# 3_Channel_Preprocessor.net
KiCad netlist of a schematic drawn in EAGLE
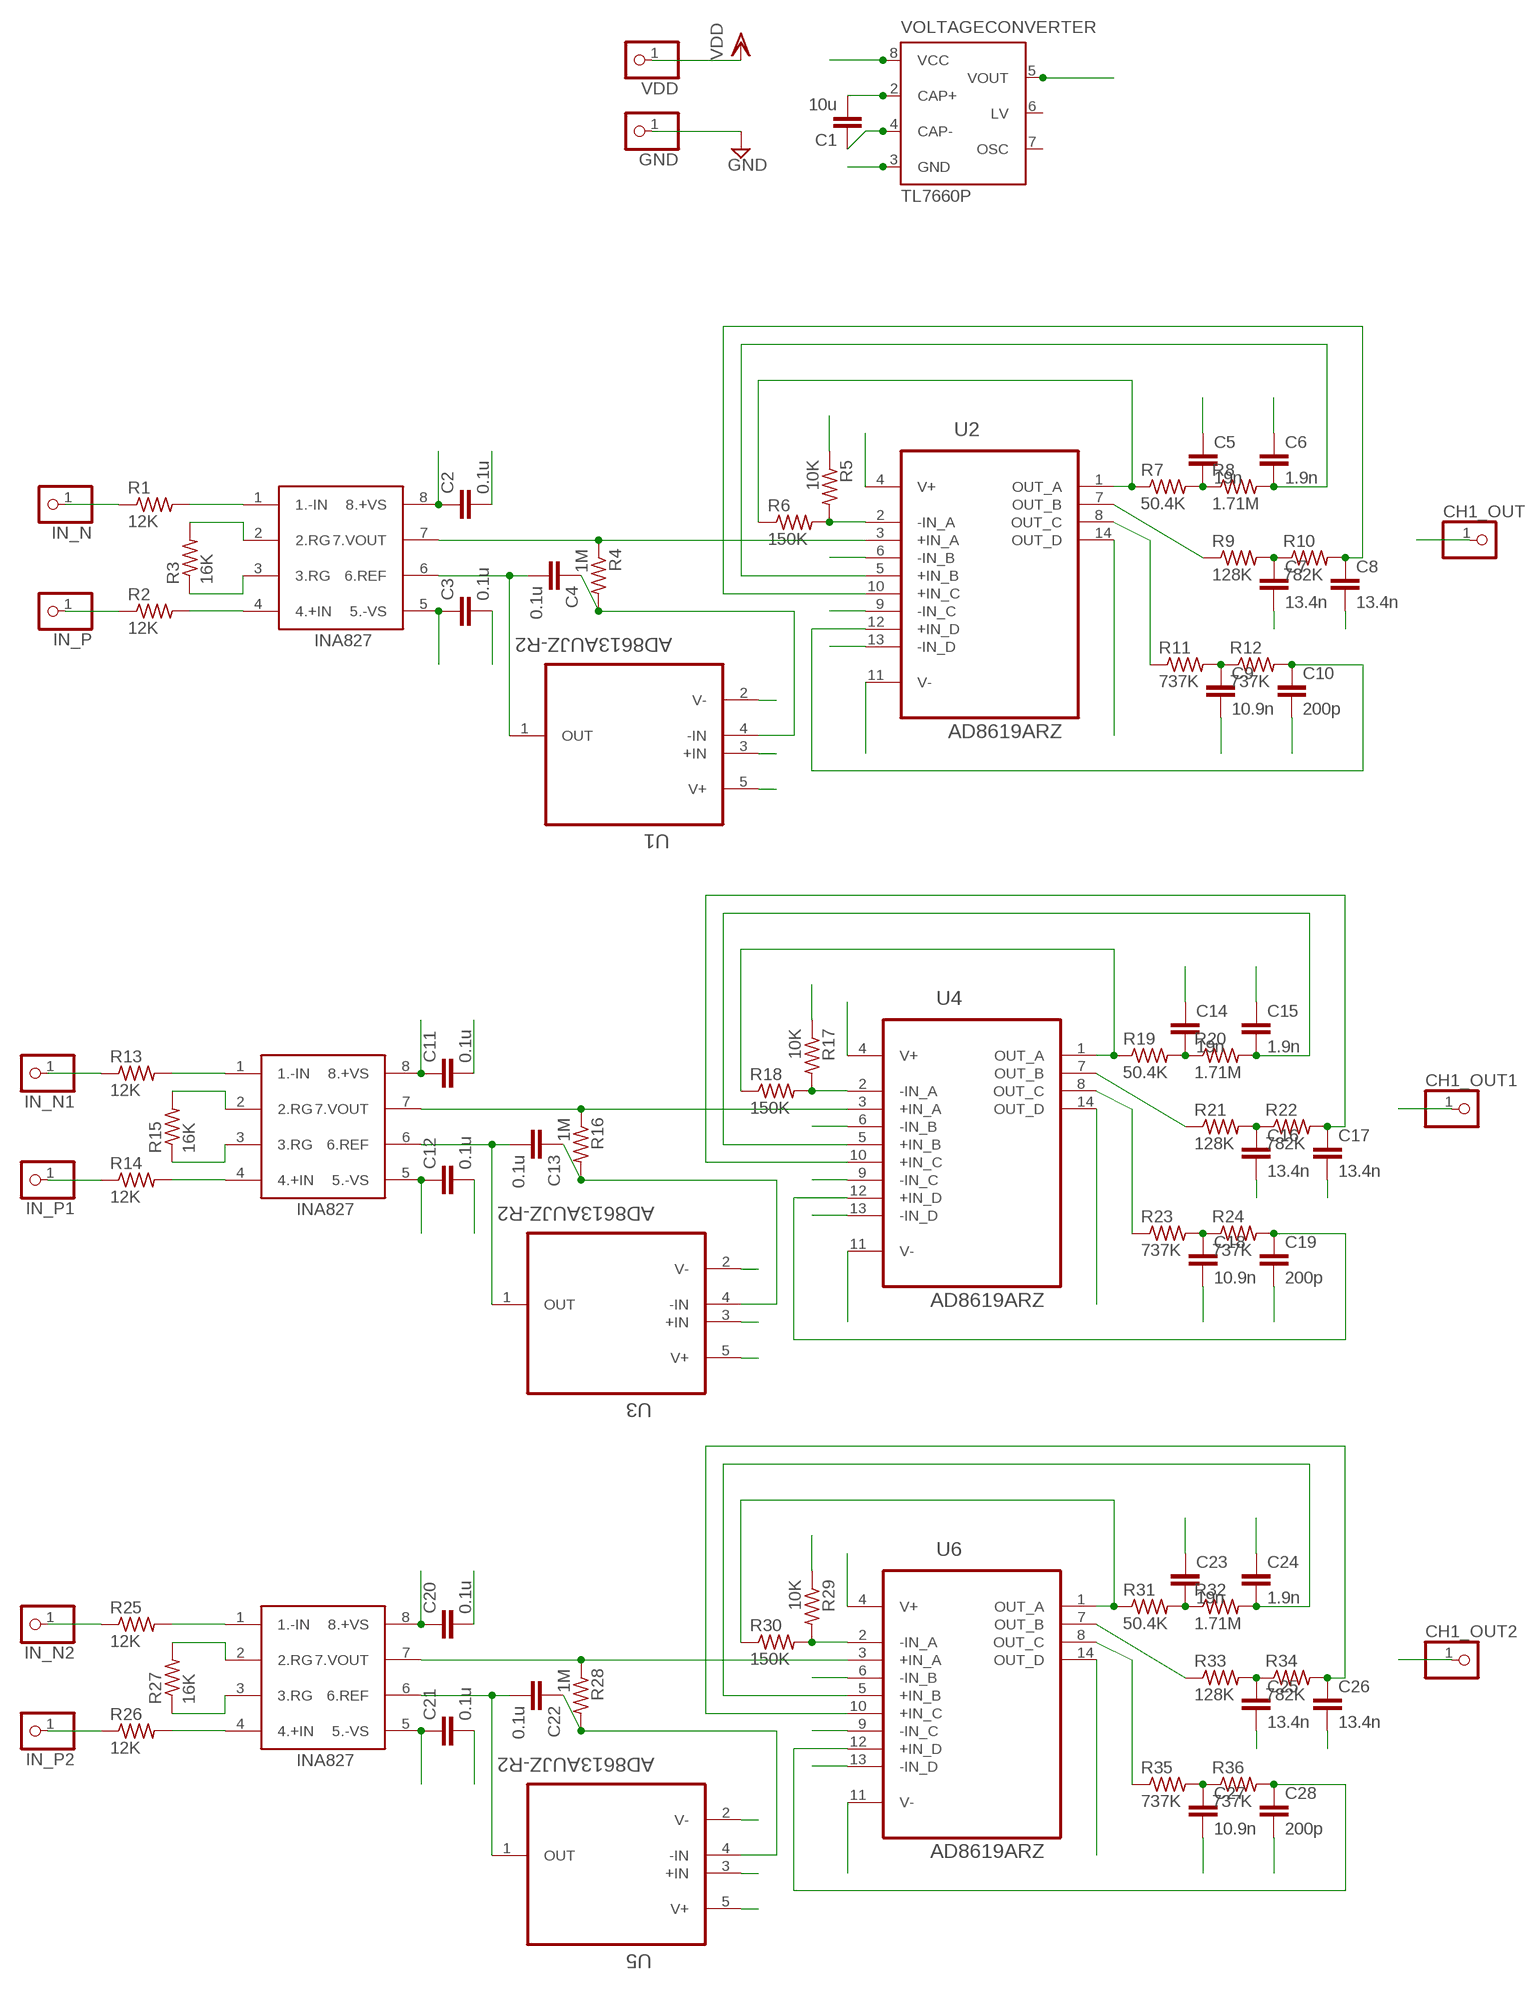
[diagram p0: schematic, sheet 1]

(export (version "E")
  (design (tool "Eeschema 10.0.6"))
  (components
    (comp (ref "C1")
      (value "10u")
      (footprint "eagle-import:C1206")
      (libsource (lib "eagle-import") (part "C-EUC1206"))
    )
    (comp (ref "C2")
      (value "0.1u")
      (footprint "eagle-import:C1206")
      (libsource (lib "eagle-import") (part "C-EUC1206"))
    )
    (comp (ref "C3")
      (value "0.1u")
      (footprint "eagle-import:C1206")
      (libsource (lib "eagle-import") (part "C-EUC1206"))
    )
    (comp (ref "C4")
      (value "0.1u")
      (footprint "eagle-import:C1206")
      (libsource (lib "eagle-import") (part "C-EUC1206"))
    )
    (comp (ref "C5")
      (value "19n")
      (footprint "eagle-import:C1206")
      (libsource (lib "eagle-import") (part "C-EUC1206"))
    )
    (comp (ref "C6")
      (value "1.9n")
      (footprint "eagle-import:C1206")
      (libsource (lib "eagle-import") (part "C-EUC1206"))
    )
    (comp (ref "C7")
      (value "13.4n")
      (footprint "eagle-import:C1206")
      (libsource (lib "eagle-import") (part "C-EUC1206"))
    )
    (comp (ref "C8")
      (value "13.4n")
      (footprint "eagle-import:C1206")
      (libsource (lib "eagle-import") (part "C-EUC1206"))
    )
    (comp (ref "C9")
      (value "10.9n")
      (footprint "eagle-import:C1206")
      (libsource (lib "eagle-import") (part "C-EUC1206"))
    )
    (comp (ref "C10")
      (value "200p")
      (footprint "eagle-import:C1206")
      (libsource (lib "eagle-import") (part "C-EUC1206"))
    )
    (comp (ref "C11")
      (value "0.1u")
      (footprint "eagle-import:C1206")
      (libsource (lib "eagle-import") (part "C-EUC1206"))
    )
    (comp (ref "C12")
      (value "0.1u")
      (footprint "eagle-import:C1206")
      (libsource (lib "eagle-import") (part "C-EUC1206"))
    )
    (comp (ref "C13")
      (value "0.1u")
      (footprint "eagle-import:C1206")
      (libsource (lib "eagle-import") (part "C-EUC1206"))
    )
    (comp (ref "C14")
      (value "19n")
      (footprint "eagle-import:C1206")
      (libsource (lib "eagle-import") (part "C-EUC1206"))
    )
    (comp (ref "C15")
      (value "1.9n")
      (footprint "eagle-import:C1206")
      (libsource (lib "eagle-import") (part "C-EUC1206"))
    )
    (comp (ref "C16")
      (value "13.4n")
      (footprint "eagle-import:C1206")
      (libsource (lib "eagle-import") (part "C-EUC1206"))
    )
    (comp (ref "C17")
      (value "13.4n")
      (footprint "eagle-import:C1206")
      (libsource (lib "eagle-import") (part "C-EUC1206"))
    )
    (comp (ref "C18")
      (value "10.9n")
      (footprint "eagle-import:C1206")
      (libsource (lib "eagle-import") (part "C-EUC1206"))
    )
    (comp (ref "C19")
      (value "200p")
      (footprint "eagle-import:C1206")
      (libsource (lib "eagle-import") (part "C-EUC1206"))
    )
    (comp (ref "C20")
      (value "0.1u")
      (footprint "eagle-import:C1206")
      (libsource (lib "eagle-import") (part "C-EUC1206"))
    )
    (comp (ref "C21")
      (value "0.1u")
      (footprint "eagle-import:C1206")
      (libsource (lib "eagle-import") (part "C-EUC1206"))
    )
    (comp (ref "C22")
      (value "0.1u")
      (footprint "eagle-import:C1206")
      (libsource (lib "eagle-import") (part "C-EUC1206"))
    )
    (comp (ref "C23")
      (value "19n")
      (footprint "eagle-import:C1206")
      (libsource (lib "eagle-import") (part "C-EUC1206"))
    )
    (comp (ref "C24")
      (value "1.9n")
      (footprint "eagle-import:C1206")
      (libsource (lib "eagle-import") (part "C-EUC1206"))
    )
    (comp (ref "C25")
      (value "13.4n")
      (footprint "eagle-import:C1206")
      (libsource (lib "eagle-import") (part "C-EUC1206"))
    )
    (comp (ref "C26")
      (value "13.4n")
      (footprint "eagle-import:C1206")
      (libsource (lib "eagle-import") (part "C-EUC1206"))
    )
    (comp (ref "C27")
      (value "10.9n")
      (footprint "eagle-import:C1206")
      (libsource (lib "eagle-import") (part "C-EUC1206"))
    )
    (comp (ref "C28")
      (value "200p")
      (footprint "eagle-import:C1206")
      (libsource (lib "eagle-import") (part "C-EUC1206"))
    )
    (comp (ref "CH1_OUT")
      (value "PINHD-1X1")
      (footprint "eagle-import:1X01")
      (libsource (lib "eagle-import") (part "PINHD-1X1"))
    )
    (comp (ref "CH1_OUT1")
      (value "PINHD-1X1")
      (footprint "eagle-import:1X01")
      (libsource (lib "eagle-import") (part "PINHD-1X1"))
    )
    (comp (ref "CH1_OUT2")
      (value "PINHD-1X1")
      (footprint "eagle-import:1X01")
      (libsource (lib "eagle-import") (part "PINHD-1X1"))
    )
    (comp (ref "GND")
      (value "PINHD-1X1")
      (footprint "eagle-import:1X01")
      (libsource (lib "eagle-import") (part "PINHD-1X1"))
    )
    (comp (ref "INA1")
      (value "INA827")
      (footprint "eagle-import:INA827")
      (libsource (lib "eagle-import") (part "INA827"))
    )
    (comp (ref "IN_N")
      (value "PINHD-1X1")
      (footprint "eagle-import:1X01")
      (libsource (lib "eagle-import") (part "PINHD-1X1"))
    )
    (comp (ref "IN_N1")
      (value "PINHD-1X1")
      (footprint "eagle-import:1X01")
      (libsource (lib "eagle-import") (part "PINHD-1X1"))
    )
    (comp (ref "IN_N2")
      (value "PINHD-1X1")
      (footprint "eagle-import:1X01")
      (libsource (lib "eagle-import") (part "PINHD-1X1"))
    )
    (comp (ref "IN_P")
      (value "PINHD-1X1")
      (footprint "eagle-import:1X01")
      (libsource (lib "eagle-import") (part "PINHD-1X1"))
    )
    (comp (ref "IN_P1")
      (value "PINHD-1X1")
      (footprint "eagle-import:1X01")
      (libsource (lib "eagle-import") (part "PINHD-1X1"))
    )
    (comp (ref "IN_P2")
      (value "PINHD-1X1")
      (footprint "eagle-import:1X01")
      (libsource (lib "eagle-import") (part "PINHD-1X1"))
    )
    (comp (ref "R1")
      (value "12K")
      (footprint "eagle-import:M1206")
      (libsource (lib "eagle-import") (part "R-US_M1206"))
    )
    (comp (ref "R2")
      (value "12K")
      (footprint "eagle-import:M1206")
      (libsource (lib "eagle-import") (part "R-US_M1206"))
    )
    (comp (ref "R3")
      (value "16K")
      (footprint "eagle-import:M1206")
      (libsource (lib "eagle-import") (part "R-US_M1206"))
    )
    (comp (ref "R4")
      (value "1M")
      (footprint "eagle-import:M1206")
      (libsource (lib "eagle-import") (part "R-US_M1206"))
    )
    (comp (ref "R5")
      (value "10K")
      (footprint "eagle-import:M1206")
      (libsource (lib "eagle-import") (part "R-US_M1206"))
    )
    (comp (ref "R6")
      (value "150K")
      (footprint "eagle-import:M1206")
      (libsource (lib "eagle-import") (part "R-US_M1206"))
    )
    (comp (ref "R7")
      (value "50.4K")
      (footprint "eagle-import:M1206")
      (libsource (lib "eagle-import") (part "R-US_M1206"))
    )
    (comp (ref "R8")
      (value "1.71M")
      (footprint "eagle-import:M1206")
      (libsource (lib "eagle-import") (part "R-US_M1206"))
    )
    (comp (ref "R9")
      (value "128K")
      (footprint "eagle-import:M1206")
      (libsource (lib "eagle-import") (part "R-US_M1206"))
    )
    (comp (ref "R10")
      (value "782K")
      (footprint "eagle-import:M1206")
      (libsource (lib "eagle-import") (part "R-US_M1206"))
    )
    (comp (ref "R11")
      (value "737K")
      (footprint "eagle-import:M1206")
      (libsource (lib "eagle-import") (part "R-US_M1206"))
    )
    (comp (ref "R12")
      (value "737K")
      (footprint "eagle-import:M1206")
      (libsource (lib "eagle-import") (part "R-US_M1206"))
    )
    (comp (ref "R13")
      (value "12K")
      (footprint "eagle-import:M1206")
      (libsource (lib "eagle-import") (part "R-US_M1206"))
    )
    (comp (ref "R14")
      (value "12K")
      (footprint "eagle-import:M1206")
      (libsource (lib "eagle-import") (part "R-US_M1206"))
    )
    (comp (ref "R15")
      (value "16K")
      (footprint "eagle-import:M1206")
      (libsource (lib "eagle-import") (part "R-US_M1206"))
    )
    (comp (ref "R16")
      (value "1M")
      (footprint "eagle-import:M1206")
      (libsource (lib "eagle-import") (part "R-US_M1206"))
    )
    (comp (ref "R17")
      (value "10K")
      (footprint "eagle-import:M1206")
      (libsource (lib "eagle-import") (part "R-US_M1206"))
    )
    (comp (ref "R18")
      (value "150K")
      (footprint "eagle-import:M1206")
      (libsource (lib "eagle-import") (part "R-US_M1206"))
    )
    (comp (ref "R19")
      (value "50.4K")
      (footprint "eagle-import:M1206")
      (libsource (lib "eagle-import") (part "R-US_M1206"))
    )
    (comp (ref "R20")
      (value "1.71M")
      (footprint "eagle-import:M1206")
      (libsource (lib "eagle-import") (part "R-US_M1206"))
    )
    (comp (ref "R21")
      (value "128K")
      (footprint "eagle-import:M1206")
      (libsource (lib "eagle-import") (part "R-US_M1206"))
    )
    (comp (ref "R22")
      (value "782K")
      (footprint "eagle-import:M1206")
      (libsource (lib "eagle-import") (part "R-US_M1206"))
    )
    (comp (ref "R23")
      (value "737K")
      (footprint "eagle-import:M1206")
      (libsource (lib "eagle-import") (part "R-US_M1206"))
    )
    (comp (ref "R24")
      (value "737K")
      (footprint "eagle-import:M1206")
      (libsource (lib "eagle-import") (part "R-US_M1206"))
    )
    (comp (ref "R25")
      (value "12K")
      (footprint "eagle-import:M1206")
      (libsource (lib "eagle-import") (part "R-US_M1206"))
    )
    (comp (ref "R26")
      (value "12K")
      (footprint "eagle-import:M1206")
      (libsource (lib "eagle-import") (part "R-US_M1206"))
    )
    (comp (ref "R27")
      (value "16K")
      (footprint "eagle-import:M1206")
      (libsource (lib "eagle-import") (part "R-US_M1206"))
    )
    (comp (ref "R28")
      (value "1M")
      (footprint "eagle-import:M1206")
      (libsource (lib "eagle-import") (part "R-US_M1206"))
    )
    (comp (ref "R29")
      (value "10K")
      (footprint "eagle-import:M1206")
      (libsource (lib "eagle-import") (part "R-US_M1206"))
    )
    (comp (ref "R30")
      (value "150K")
      (footprint "eagle-import:M1206")
      (libsource (lib "eagle-import") (part "R-US_M1206"))
    )
    (comp (ref "R31")
      (value "50.4K")
      (footprint "eagle-import:M1206")
      (libsource (lib "eagle-import") (part "R-US_M1206"))
    )
    (comp (ref "R32")
      (value "1.71M")
      (footprint "eagle-import:M1206")
      (libsource (lib "eagle-import") (part "R-US_M1206"))
    )
    (comp (ref "R33")
      (value "128K")
      (footprint "eagle-import:M1206")
      (libsource (lib "eagle-import") (part "R-US_M1206"))
    )
    (comp (ref "R34")
      (value "782K")
      (footprint "eagle-import:M1206")
      (libsource (lib "eagle-import") (part "R-US_M1206"))
    )
    (comp (ref "R35")
      (value "737K")
      (footprint "eagle-import:M1206")
      (libsource (lib "eagle-import") (part "R-US_M1206"))
    )
    (comp (ref "R36")
      (value "737K")
      (footprint "eagle-import:M1206")
      (libsource (lib "eagle-import") (part "R-US_M1206"))
    )
    (comp (ref "U$2")
      (value "INA827")
      (footprint "eagle-import:INA827")
      (libsource (lib "eagle-import") (part "INA827"))
    )
    (comp (ref "U$3")
      (value "INA827")
      (footprint "eagle-import:INA827")
      (libsource (lib "eagle-import") (part "INA827"))
    )
    (comp (ref "U1")
      (value "AD8613AUJZ-R2")
      (footprint "eagle-import:SOT95P280X100-5N")
      (fields (field (name "MF") "Analog Devices"))
      (libsource (lib "eagle-import") (part "AD8613AUJZ-R2"))
    )
    (comp (ref "U2")
      (value "AD8619ARZ")
      (footprint "eagle-import:SOIC127P600X175-14N")
      (fields (field (name "MF") "Analog Devices"))
      (libsource (lib "eagle-import") (part "AD8619ARZ"))
    )
    (comp (ref "U3")
      (value "AD8613AUJZ-R2")
      (footprint "eagle-import:SOT95P280X100-5N")
      (fields (field (name "MF") "Analog Devices"))
      (libsource (lib "eagle-import") (part "AD8613AUJZ-R2"))
    )
    (comp (ref "U4")
      (value "AD8619ARZ")
      (footprint "eagle-import:SOIC127P600X175-14N")
      (fields (field (name "MF") "Analog Devices"))
      (libsource (lib "eagle-import") (part "AD8619ARZ"))
    )
    (comp (ref "U5")
      (value "AD8613AUJZ-R2")
      (footprint "eagle-import:SOT95P280X100-5N")
      (fields (field (name "MF") "Analog Devices"))
      (libsource (lib "eagle-import") (part "AD8613AUJZ-R2"))
    )
    (comp (ref "U6")
      (value "AD8619ARZ")
      (footprint "eagle-import:SOIC127P600X175-14N")
      (fields (field (name "MF") "Analog Devices"))
      (libsource (lib "eagle-import") (part "AD8619ARZ"))
    )
    (comp (ref "VDD")
      (value "PINHD-1X1")
      (footprint "eagle-import:1X01")
      (libsource (lib "eagle-import") (part "PINHD-1X1"))
    )
    (comp (ref "VOLTAGECONVERTER")
      (value "TL7660P")
      (footprint "eagle-import:DIL08")
      (fields (field (name "MPN") "TL7660CP"))
      (libsource (lib "eagle-import") (part "TL7660P"))
    )
  )
  (nets
    (net (code "1") (name "/OUT_B") (class "Default")
      (node (ref "C5") (pin "1") (pinfunction "1_1") (pintype "passive"))
      (node (ref "R9") (pin "1") (pinfunction "1_1") (pintype "passive"))
      (node (ref "U2") (pin "6") (pinfunction "-IN_B_6") (pintype "input"))
      (node (ref "U2") (pin "7") (pinfunction "OUT_B_7") (pintype "output"))
    )
    (net (code "2") (name "/OUT_B1") (class "Default")
      (node (ref "C14") (pin "1") (pinfunction "1_1") (pintype "passive"))
      (node (ref "R21") (pin "1") (pinfunction "1_1") (pintype "passive"))
      (node (ref "U4") (pin "6") (pinfunction "-IN_B_6") (pintype "input"))
      (node (ref "U4") (pin "7") (pinfunction "OUT_B_7") (pintype "output"))
    )
    (net (code "3") (name "/OUT_B2") (class "Default")
      (node (ref "C23") (pin "1") (pinfunction "1_1") (pintype "passive"))
      (node (ref "R33") (pin "1") (pinfunction "1_1") (pintype "passive"))
      (node (ref "U6") (pin "6") (pinfunction "-IN_B_6") (pintype "input"))
      (node (ref "U6") (pin "7") (pinfunction "OUT_B_7") (pintype "output"))
    )
    (net (code "4") (name "/OUT_C") (class "Default")
      (node (ref "C7") (pin "2") (pinfunction "2_2") (pintype "passive"))
      (node (ref "R11") (pin "1") (pinfunction "1_1") (pintype "passive"))
      (node (ref "U2") (pin "8") (pinfunction "OUT_C_8") (pintype "output"))
      (node (ref "U2") (pin "9") (pinfunction "-IN_C_9") (pintype "input"))
    )
    (net (code "5") (name "/OUT_C1") (class "Default")
      (node (ref "C16") (pin "2") (pinfunction "2_2") (pintype "passive"))
      (node (ref "R23") (pin "1") (pinfunction "1_1") (pintype "passive"))
      (node (ref "U4") (pin "8") (pinfunction "OUT_C_8") (pintype "output"))
      (node (ref "U4") (pin "9") (pinfunction "-IN_C_9") (pintype "input"))
    )
    (net (code "6") (name "/OUT_C2") (class "Default")
      (node (ref "C25") (pin "2") (pinfunction "2_2") (pintype "passive"))
      (node (ref "R35") (pin "1") (pinfunction "1_1") (pintype "passive"))
      (node (ref "U6") (pin "8") (pinfunction "OUT_C_8") (pintype "output"))
      (node (ref "U6") (pin "9") (pinfunction "-IN_C_9") (pintype "input"))
    )
    (net (code "7") (name "/OUT_D") (class "Default")
      (node (ref "C9") (pin "2") (pinfunction "2_2") (pintype "passive"))
      (node (ref "CH1_OUT") (pin "1") (pinfunction "1_1") (pintype "passive"))
      (node (ref "U2") (pin "13") (pinfunction "-IN_D_13") (pintype "input"))
      (node (ref "U2") (pin "14") (pinfunction "OUT_D_14") (pintype "output"))
    )
    (net (code "8") (name "/OUT_D1") (class "Default")
      (node (ref "C18") (pin "2") (pinfunction "2_2") (pintype "passive"))
      (node (ref "CH1_OUT1") (pin "1") (pinfunction "1_1") (pintype "passive"))
      (node (ref "U4") (pin "13") (pinfunction "-IN_D_13") (pintype "input"))
      (node (ref "U4") (pin "14") (pinfunction "OUT_D_14") (pintype "output"))
    )
    (net (code "9") (name "/OUT_D2") (class "Default")
      (node (ref "C27") (pin "2") (pinfunction "2_2") (pintype "passive"))
      (node (ref "CH1_OUT2") (pin "1") (pinfunction "1_1") (pintype "passive"))
      (node (ref "U6") (pin "13") (pinfunction "-IN_D_13") (pintype "input"))
      (node (ref "U6") (pin "14") (pinfunction "OUT_D_14") (pintype "output"))
    )
    (net (code "10") (name "/VDD-") (class "Default")
      (node (ref "C12") (pin "1") (pinfunction "1_1") (pintype "passive"))
      (node (ref "C21") (pin "1") (pinfunction "1_1") (pintype "passive"))
      (node (ref "C3") (pin "1") (pinfunction "1_1") (pintype "passive"))
      (node (ref "INA1") (pin "5") (pinfunction "5.-VS_5") (pintype "bidirectional"))
      (node (ref "U$2") (pin "5") (pinfunction "5.-VS_5") (pintype "bidirectional"))
      (node (ref "U$3") (pin "5") (pinfunction "5.-VS_5") (pintype "bidirectional"))
      (node (ref "U1") (pin "2") (pinfunction "V-_2") (pintype "passive"))
      (node (ref "U2") (pin "11") (pinfunction "V-_11") (pintype "power_in"))
      (node (ref "U3") (pin "2") (pinfunction "V-_2") (pintype "passive"))
      (node (ref "U4") (pin "11") (pinfunction "V-_11") (pintype "power_in"))
      (node (ref "U5") (pin "2") (pinfunction "V-_2") (pintype "passive"))
      (node (ref "U6") (pin "11") (pinfunction "V-_11") (pintype "power_in"))
      (node (ref "VOLTAGECONVERTER") (pin "5") (pinfunction "VOUT_5") (pintype "passive"))
    )
    (net (code "11") (name "GND") (class "Default")
      (node (ref "C10") (pin "2") (pinfunction "2_2") (pintype "passive"))
      (node (ref "C11") (pin "2") (pinfunction "2_2") (pintype "passive"))
      (node (ref "C12") (pin "2") (pinfunction "2_2") (pintype "passive"))
      (node (ref "C15") (pin "1") (pinfunction "1_1") (pintype "passive"))
      (node (ref "C17") (pin "2") (pinfunction "2_2") (pintype "passive"))
      (node (ref "C19") (pin "2") (pinfunction "2_2") (pintype "passive"))
      (node (ref "C2") (pin "2") (pinfunction "2_2") (pintype "passive"))
      (node (ref "C20") (pin "2") (pinfunction "2_2") (pintype "passive"))
      (node (ref "C21") (pin "2") (pinfunction "2_2") (pintype "passive"))
      (node (ref "C24") (pin "1") (pinfunction "1_1") (pintype "passive"))
      (node (ref "C26") (pin "2") (pinfunction "2_2") (pintype "passive"))
      (node (ref "C28") (pin "2") (pinfunction "2_2") (pintype "passive"))
      (node (ref "C3") (pin "2") (pinfunction "2_2") (pintype "passive"))
      (node (ref "C6") (pin "1") (pinfunction "1_1") (pintype "passive"))
      (node (ref "C8") (pin "2") (pinfunction "2_2") (pintype "passive"))
      (node (ref "GND") (pin "1") (pinfunction "1_1") (pintype "passive"))
      (node (ref "R17") (pin "1") (pinfunction "1_1") (pintype "passive"))
      (node (ref "R29") (pin "1") (pinfunction "1_1") (pintype "passive"))
      (node (ref "R5") (pin "1") (pinfunction "1_1") (pintype "passive"))
      (node (ref "U1") (pin "3") (pinfunction "+IN_3") (pintype "passive"))
      (node (ref "U3") (pin "3") (pinfunction "+IN_3") (pintype "passive"))
      (node (ref "U5") (pin "3") (pinfunction "+IN_3") (pintype "passive"))
      (node (ref "VOLTAGECONVERTER") (pin "3") (pinfunction "GND_3") (pintype "power_in"))
    )
    (net (code "12") (name "Net-(C5-Pad2)") (class "Default")
      (node (ref "C5") (pin "2") (pinfunction "2_2") (pintype "passive"))
      (node (ref "R7") (pin "2") (pinfunction "2_2") (pintype "passive"))
      (node (ref "R8") (pin "1") (pinfunction "1_1") (pintype "passive"))
    )
    (net (code "13") (name "Net-(C7-Pad1)") (class "Default")
      (node (ref "C7") (pin "1") (pinfunction "1_1") (pintype "passive"))
      (node (ref "R10") (pin "1") (pinfunction "1_1") (pintype "passive"))
      (node (ref "R9") (pin "2") (pinfunction "2_2") (pintype "passive"))
    )
    (net (code "14") (name "Net-(C9-Pad1)") (class "Default")
      (node (ref "C9") (pin "1") (pinfunction "1_1") (pintype "passive"))
      (node (ref "R11") (pin "2") (pinfunction "2_2") (pintype "passive"))
      (node (ref "R12") (pin "1") (pinfunction "1_1") (pintype "passive"))
    )
    (net (code "15") (name "Net-(C14-Pad2)") (class "Default")
      (node (ref "C14") (pin "2") (pinfunction "2_2") (pintype "passive"))
      (node (ref "R19") (pin "2") (pinfunction "2_2") (pintype "passive"))
      (node (ref "R20") (pin "1") (pinfunction "1_1") (pintype "passive"))
    )
    (net (code "16") (name "Net-(C16-Pad1)") (class "Default")
      (node (ref "C16") (pin "1") (pinfunction "1_1") (pintype "passive"))
      (node (ref "R21") (pin "2") (pinfunction "2_2") (pintype "passive"))
      (node (ref "R22") (pin "1") (pinfunction "1_1") (pintype "passive"))
    )
    (net (code "17") (name "Net-(C18-Pad1)") (class "Default")
      (node (ref "C18") (pin "1") (pinfunction "1_1") (pintype "passive"))
      (node (ref "R23") (pin "2") (pinfunction "2_2") (pintype "passive"))
      (node (ref "R24") (pin "1") (pinfunction "1_1") (pintype "passive"))
    )
    (net (code "18") (name "Net-(C23-Pad2)") (class "Default")
      (node (ref "C23") (pin "2") (pinfunction "2_2") (pintype "passive"))
      (node (ref "R31") (pin "2") (pinfunction "2_2") (pintype "passive"))
      (node (ref "R32") (pin "1") (pinfunction "1_1") (pintype "passive"))
    )
    (net (code "19") (name "Net-(C25-Pad1)") (class "Default")
      (node (ref "C25") (pin "1") (pinfunction "1_1") (pintype "passive"))
      (node (ref "R33") (pin "2") (pinfunction "2_2") (pintype "passive"))
      (node (ref "R34") (pin "1") (pinfunction "1_1") (pintype "passive"))
    )
    (net (code "20") (name "Net-(C27-Pad1)") (class "Default")
      (node (ref "C27") (pin "1") (pinfunction "1_1") (pintype "passive"))
      (node (ref "R35") (pin "2") (pinfunction "2_2") (pintype "passive"))
      (node (ref "R36") (pin "1") (pinfunction "1_1") (pintype "passive"))
    )
    (net (code "21") (name "Net-(INA1-1.-IN)") (class "Default")
      (node (ref "INA1") (pin "1") (pinfunction "1.-IN_1") (pintype "bidirectional"))
      (node (ref "R1") (pin "2") (pinfunction "2_2") (pintype "passive"))
    )
    (net (code "22") (name "Net-(INA1-2.RG)") (class "Default")
      (node (ref "INA1") (pin "2") (pinfunction "2.RG_2") (pintype "bidirectional"))
      (node (ref "R3") (pin "2") (pinfunction "2_2") (pintype "passive"))
    )
    (net (code "23") (name "Net-(INA1-3.RG)") (class "Default")
      (node (ref "INA1") (pin "3") (pinfunction "3.RG_3") (pintype "bidirectional"))
      (node (ref "R3") (pin "1") (pinfunction "1_1") (pintype "passive"))
    )
    (net (code "24") (name "Net-(INA1-4.+IN)") (class "Default")
      (node (ref "INA1") (pin "4") (pinfunction "4.+IN_4") (pintype "bidirectional"))
      (node (ref "R2") (pin "2") (pinfunction "2_2") (pintype "passive"))
    )
    (net (code "25") (name "Net-(INA1-6.REF)") (class "Default")
      (node (ref "C4") (pin "2") (pinfunction "2_2") (pintype "passive"))
      (node (ref "INA1") (pin "6") (pinfunction "6.REF_6") (pintype "bidirectional"))
      (node (ref "U1") (pin "1") (pinfunction "OUT_1") (pintype "passive"))
    )
    (net (code "26") (name "Net-(INA1-7.VOUT)") (class "Default")
      (node (ref "INA1") (pin "7") (pinfunction "7.VOUT_7") (pintype "bidirectional"))
      (node (ref "R4") (pin "1") (pinfunction "1_1") (pintype "passive"))
      (node (ref "U2") (pin "3") (pinfunction "+IN_A_3") (pintype "input"))
    )
    (net (code "27") (name "Net-(IN_N-Pad1)") (class "Default")
      (node (ref "IN_N") (pin "1") (pinfunction "1_1") (pintype "passive"))
      (node (ref "R1") (pin "1") (pinfunction "1_1") (pintype "passive"))
    )
    (net (code "28") (name "Net-(IN_N1-Pad1)") (class "Default")
      (node (ref "IN_N1") (pin "1") (pinfunction "1_1") (pintype "passive"))
      (node (ref "R13") (pin "1") (pinfunction "1_1") (pintype "passive"))
    )
    (net (code "29") (name "Net-(IN_N2-Pad1)") (class "Default")
      (node (ref "IN_N2") (pin "1") (pinfunction "1_1") (pintype "passive"))
      (node (ref "R25") (pin "1") (pinfunction "1_1") (pintype "passive"))
    )
    (net (code "30") (name "Net-(IN_P-Pad1)") (class "Default")
      (node (ref "IN_P") (pin "1") (pinfunction "1_1") (pintype "passive"))
      (node (ref "R2") (pin "1") (pinfunction "1_1") (pintype "passive"))
    )
    (net (code "31") (name "Net-(IN_P1-Pad1)") (class "Default")
      (node (ref "IN_P1") (pin "1") (pinfunction "1_1") (pintype "passive"))
      (node (ref "R14") (pin "1") (pinfunction "1_1") (pintype "passive"))
    )
    (net (code "32") (name "Net-(IN_P2-Pad1)") (class "Default")
      (node (ref "IN_P2") (pin "1") (pinfunction "1_1") (pintype "passive"))
      (node (ref "R26") (pin "1") (pinfunction "1_1") (pintype "passive"))
    )
    (net (code "33") (name "Net-(U$2-1.-IN)") (class "Default")
      (node (ref "R13") (pin "2") (pinfunction "2_2") (pintype "passive"))
      (node (ref "U$2") (pin "1") (pinfunction "1.-IN_1") (pintype "bidirectional"))
    )
    (net (code "34") (name "Net-(U$2-2.RG)") (class "Default")
      (node (ref "R15") (pin "2") (pinfunction "2_2") (pintype "passive"))
      (node (ref "U$2") (pin "2") (pinfunction "2.RG_2") (pintype "bidirectional"))
    )
    (net (code "35") (name "Net-(U$2-3.RG)") (class "Default")
      (node (ref "R15") (pin "1") (pinfunction "1_1") (pintype "passive"))
      (node (ref "U$2") (pin "3") (pinfunction "3.RG_3") (pintype "bidirectional"))
    )
    (net (code "36") (name "Net-(U$2-4.+IN)") (class "Default")
      (node (ref "R14") (pin "2") (pinfunction "2_2") (pintype "passive"))
      (node (ref "U$2") (pin "4") (pinfunction "4.+IN_4") (pintype "bidirectional"))
    )
    (net (code "37") (name "Net-(U$2-6.REF)") (class "Default")
      (node (ref "C13") (pin "2") (pinfunction "2_2") (pintype "passive"))
      (node (ref "U$2") (pin "6") (pinfunction "6.REF_6") (pintype "bidirectional"))
      (node (ref "U3") (pin "1") (pinfunction "OUT_1") (pintype "passive"))
    )
    (net (code "38") (name "Net-(U$2-7.VOUT)") (class "Default")
      (node (ref "R16") (pin "1") (pinfunction "1_1") (pintype "passive"))
      (node (ref "U$2") (pin "7") (pinfunction "7.VOUT_7") (pintype "bidirectional"))
      (node (ref "U4") (pin "3") (pinfunction "+IN_A_3") (pintype "input"))
    )
    (net (code "39") (name "Net-(U$3-1.-IN)") (class "Default")
      (node (ref "R25") (pin "2") (pinfunction "2_2") (pintype "passive"))
      (node (ref "U$3") (pin "1") (pinfunction "1.-IN_1") (pintype "bidirectional"))
    )
    (net (code "40") (name "Net-(U$3-2.RG)") (class "Default")
      (node (ref "R27") (pin "2") (pinfunction "2_2") (pintype "passive"))
      (node (ref "U$3") (pin "2") (pinfunction "2.RG_2") (pintype "bidirectional"))
    )
    (net (code "41") (name "Net-(U$3-3.RG)") (class "Default")
      (node (ref "R27") (pin "1") (pinfunction "1_1") (pintype "passive"))
      (node (ref "U$3") (pin "3") (pinfunction "3.RG_3") (pintype "bidirectional"))
    )
    (net (code "42") (name "Net-(U$3-4.+IN)") (class "Default")
      (node (ref "R26") (pin "2") (pinfunction "2_2") (pintype "passive"))
      (node (ref "U$3") (pin "4") (pinfunction "4.+IN_4") (pintype "bidirectional"))
    )
    (net (code "43") (name "Net-(U$3-6.REF)") (class "Default")
      (node (ref "C22") (pin "2") (pinfunction "2_2") (pintype "passive"))
      (node (ref "U$3") (pin "6") (pinfunction "6.REF_6") (pintype "bidirectional"))
      (node (ref "U5") (pin "1") (pinfunction "OUT_1") (pintype "passive"))
    )
    (net (code "44") (name "Net-(U$3-7.VOUT)") (class "Default")
      (node (ref "R28") (pin "1") (pinfunction "1_1") (pintype "passive"))
      (node (ref "U$3") (pin "7") (pinfunction "7.VOUT_7") (pintype "bidirectional"))
      (node (ref "U6") (pin "3") (pinfunction "+IN_A_3") (pintype "input"))
    )
    (net (code "45") (name "Net-(U1--IN)") (class "Default")
      (node (ref "C4") (pin "1") (pinfunction "1_1") (pintype "passive"))
      (node (ref "R4") (pin "2") (pinfunction "2_2") (pintype "passive"))
      (node (ref "U1") (pin "4") (pinfunction "-IN_4") (pintype "passive"))
    )
    (net (code "46") (name "Net-(U2-+IN_B)") (class "Default")
      (node (ref "C6") (pin "2") (pinfunction "2_2") (pintype "passive"))
      (node (ref "R8") (pin "2") (pinfunction "2_2") (pintype "passive"))
      (node (ref "U2") (pin "5") (pinfunction "+IN_B_5") (pintype "input"))
    )
    (net (code "47") (name "Net-(U2-+IN_C)") (class "Default")
      (node (ref "C8") (pin "1") (pinfunction "1_1") (pintype "passive"))
      (node (ref "R10") (pin "2") (pinfunction "2_2") (pintype "passive"))
      (node (ref "U2") (pin "10") (pinfunction "+IN_C_10") (pintype "input"))
    )
    (net (code "48") (name "Net-(U2-+IN_D)") (class "Default")
      (node (ref "C10") (pin "1") (pinfunction "1_1") (pintype "passive"))
      (node (ref "R12") (pin "2") (pinfunction "2_2") (pintype "passive"))
      (node (ref "U2") (pin "12") (pinfunction "+IN_D_12") (pintype "input"))
    )
    (net (code "49") (name "Net-(U2--IN_A)") (class "Default")
      (node (ref "R5") (pin "2") (pinfunction "2_2") (pintype "passive"))
      (node (ref "R6") (pin "2") (pinfunction "2_2") (pintype "passive"))
      (node (ref "U2") (pin "2") (pinfunction "-IN_A_2") (pintype "input"))
    )
    (net (code "50") (name "Net-(U2-OUT_A)") (class "Default")
      (node (ref "R6") (pin "1") (pinfunction "1_1") (pintype "passive"))
      (node (ref "R7") (pin "1") (pinfunction "1_1") (pintype "passive"))
      (node (ref "U2") (pin "1") (pinfunction "OUT_A_1") (pintype "output"))
    )
    (net (code "51") (name "Net-(U3--IN)") (class "Default")
      (node (ref "C13") (pin "1") (pinfunction "1_1") (pintype "passive"))
      (node (ref "R16") (pin "2") (pinfunction "2_2") (pintype "passive"))
      (node (ref "U3") (pin "4") (pinfunction "-IN_4") (pintype "passive"))
    )
    (net (code "52") (name "Net-(U4-+IN_B)") (class "Default")
      (node (ref "C15") (pin "2") (pinfunction "2_2") (pintype "passive"))
      (node (ref "R20") (pin "2") (pinfunction "2_2") (pintype "passive"))
      (node (ref "U4") (pin "5") (pinfunction "+IN_B_5") (pintype "input"))
    )
    (net (code "53") (name "Net-(U4-+IN_C)") (class "Default")
      (node (ref "C17") (pin "1") (pinfunction "1_1") (pintype "passive"))
      (node (ref "R22") (pin "2") (pinfunction "2_2") (pintype "passive"))
      (node (ref "U4") (pin "10") (pinfunction "+IN_C_10") (pintype "input"))
    )
    (net (code "54") (name "Net-(U4-+IN_D)") (class "Default")
      (node (ref "C19") (pin "1") (pinfunction "1_1") (pintype "passive"))
      (node (ref "R24") (pin "2") (pinfunction "2_2") (pintype "passive"))
      (node (ref "U4") (pin "12") (pinfunction "+IN_D_12") (pintype "input"))
    )
    (net (code "55") (name "Net-(U4--IN_A)") (class "Default")
      (node (ref "R17") (pin "2") (pinfunction "2_2") (pintype "passive"))
      (node (ref "R18") (pin "2") (pinfunction "2_2") (pintype "passive"))
      (node (ref "U4") (pin "2") (pinfunction "-IN_A_2") (pintype "input"))
    )
    (net (code "56") (name "Net-(U4-OUT_A)") (class "Default")
      (node (ref "R18") (pin "1") (pinfunction "1_1") (pintype "passive"))
      (node (ref "R19") (pin "1") (pinfunction "1_1") (pintype "passive"))
      (node (ref "U4") (pin "1") (pinfunction "OUT_A_1") (pintype "output"))
    )
    (net (code "57") (name "Net-(U5--IN)") (class "Default")
      (node (ref "C22") (pin "1") (pinfunction "1_1") (pintype "passive"))
      (node (ref "R28") (pin "2") (pinfunction "2_2") (pintype "passive"))
      (node (ref "U5") (pin "4") (pinfunction "-IN_4") (pintype "passive"))
    )
    (net (code "58") (name "Net-(U6-+IN_B)") (class "Default")
      (node (ref "C24") (pin "2") (pinfunction "2_2") (pintype "passive"))
      (node (ref "R32") (pin "2") (pinfunction "2_2") (pintype "passive"))
      (node (ref "U6") (pin "5") (pinfunction "+IN_B_5") (pintype "input"))
    )
    (net (code "59") (name "Net-(U6-+IN_C)") (class "Default")
      (node (ref "C26") (pin "1") (pinfunction "1_1") (pintype "passive"))
      (node (ref "R34") (pin "2") (pinfunction "2_2") (pintype "passive"))
      (node (ref "U6") (pin "10") (pinfunction "+IN_C_10") (pintype "input"))
    )
    (net (code "60") (name "Net-(U6-+IN_D)") (class "Default")
      (node (ref "C28") (pin "1") (pinfunction "1_1") (pintype "passive"))
      (node (ref "R36") (pin "2") (pinfunction "2_2") (pintype "passive"))
      (node (ref "U6") (pin "12") (pinfunction "+IN_D_12") (pintype "input"))
    )
    (net (code "61") (name "Net-(U6--IN_A)") (class "Default")
      (node (ref "R29") (pin "2") (pinfunction "2_2") (pintype "passive"))
      (node (ref "R30") (pin "2") (pinfunction "2_2") (pintype "passive"))
      (node (ref "U6") (pin "2") (pinfunction "-IN_A_2") (pintype "input"))
    )
    (net (code "62") (name "Net-(U6-OUT_A)") (class "Default")
      (node (ref "R30") (pin "1") (pinfunction "1_1") (pintype "passive"))
      (node (ref "R31") (pin "1") (pinfunction "1_1") (pintype "passive"))
      (node (ref "U6") (pin "1") (pinfunction "OUT_A_1") (pintype "output"))
    )
    (net (code "63") (name "Net-(VOLTAGECONVERTER-CAP+)") (class "Default")
      (node (ref "C1") (pin "2") (pinfunction "2_2") (pintype "passive"))
      (node (ref "VOLTAGECONVERTER") (pin "2") (pinfunction "CAP+_2") (pintype "passive"))
    )
    (net (code "64") (name "Net-(VOLTAGECONVERTER-CAP-)") (class "Default")
      (node (ref "C1") (pin "1") (pinfunction "1_1") (pintype "passive"))
      (node (ref "VOLTAGECONVERTER") (pin "4") (pinfunction "CAP-_4") (pintype "passive"))
    )
    (net (code "65") (name "VDD") (class "Default")
      (node (ref "C11") (pin "1") (pinfunction "1_1") (pintype "passive"))
      (node (ref "C2") (pin "1") (pinfunction "1_1") (pintype "passive"))
      (node (ref "C20") (pin "1") (pinfunction "1_1") (pintype "passive"))
      (node (ref "INA1") (pin "8") (pinfunction "8.+VS_8") (pintype "bidirectional"))
      (node (ref "U$2") (pin "8") (pinfunction "8.+VS_8") (pintype "bidirectional"))
      (node (ref "U$3") (pin "8") (pinfunction "8.+VS_8") (pintype "bidirectional"))
      (node (ref "U1") (pin "5") (pinfunction "V+_5") (pintype "passive"))
      (node (ref "U2") (pin "4") (pinfunction "V+_4") (pintype "power_in"))
      (node (ref "U3") (pin "5") (pinfunction "V+_5") (pintype "passive"))
      (node (ref "U4") (pin "4") (pinfunction "V+_4") (pintype "power_in"))
      (node (ref "U5") (pin "5") (pinfunction "V+_5") (pintype "passive"))
      (node (ref "U6") (pin "4") (pinfunction "V+_4") (pintype "power_in"))
      (node (ref "VDD") (pin "1") (pinfunction "1_1") (pintype "passive"))
      (node (ref "VOLTAGECONVERTER") (pin "8") (pinfunction "VCC_8") (pintype "power_in"))
    )
    (net (code "66") (name "unconnected-(VOLTAGECONVERTER-LV-Pad6)") (class "Default")
      (node (ref "VOLTAGECONVERTER") (pin "6") (pinfunction "LV_6") (pintype "passive"))
    )
    (net (code "67") (name "unconnected-(VOLTAGECONVERTER-OSC-Pad7)") (class "Default")
      (node (ref "VOLTAGECONVERTER") (pin "7") (pinfunction "OSC_7") (pintype "input"))
    )
  )
)
